# Digital_Inputs.net
KiCad netlist of a schematic drawn in Altium Designer
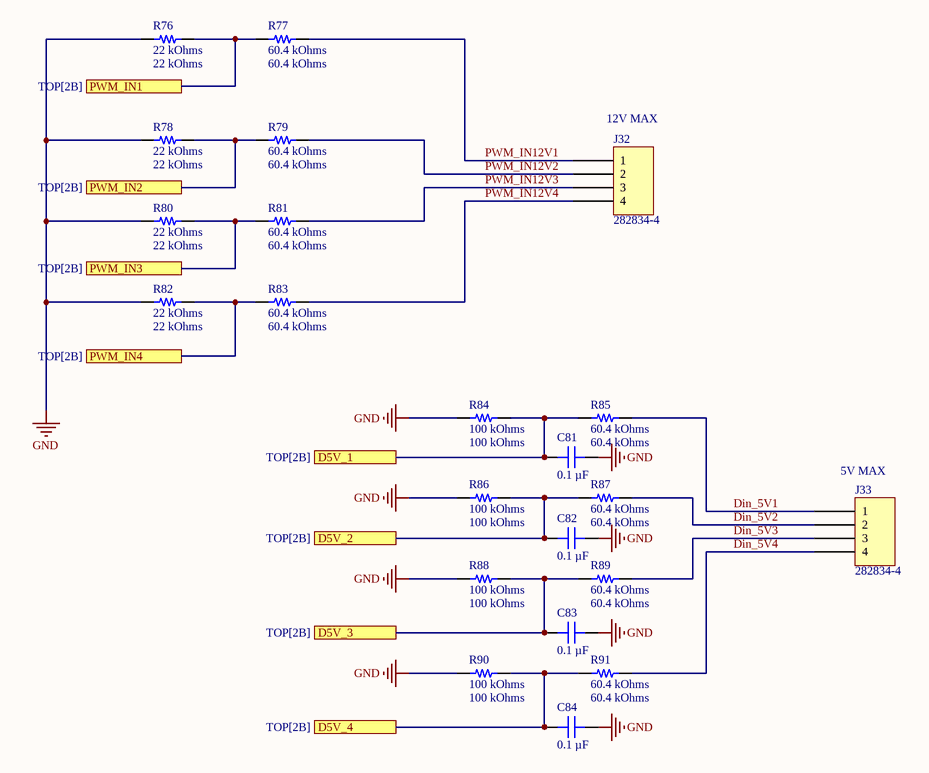
[diagram p0: Digital Inputs.SchDoc]

(export (version "E")
  (design (tool "Eeschema 10.0.6"))
  (components
    (comp (ref "C81")
      (value "0.1 µF")
      (footprint "CAP 0603_1608")
      (description "CAP CER 0.1UF 6.3V X7R 0603")
      (fields
        (field (name "PART NUMBER") "6R3X14W104MV4T")
        (field (name "MANUFACTURER") "Johanson Dielectrics Inc.")
      )
      (libsource (lib "altium_library") (part "Capacitor"))
    )
    (comp (ref "C82")
      (value "0.1 µF")
      (footprint "CAP 0603_1608")
      (description "CAP CER 0.1UF 6.3V X7R 0603")
      (fields
        (field (name "PART NUMBER") "6R3X14W104MV4T")
        (field (name "MANUFACTURER") "Johanson Dielectrics Inc.")
      )
      (libsource (lib "altium_library") (part "Capacitor"))
    )
    (comp (ref "C83")
      (value "0.1 µF")
      (footprint "CAP 0603_1608")
      (description "CAP CER 0.1UF 6.3V X7R 0603")
      (fields
        (field (name "PART NUMBER") "6R3X14W104MV4T")
        (field (name "MANUFACTURER") "Johanson Dielectrics Inc.")
      )
      (libsource (lib "altium_library") (part "Capacitor"))
    )
    (comp (ref "C84")
      (value "0.1 µF")
      (footprint "CAP 0603_1608")
      (description "CAP CER 0.1UF 6.3V X7R 0603")
      (fields
        (field (name "PART NUMBER") "6R3X14W104MV4T")
        (field (name "MANUFACTURER") "Johanson Dielectrics Inc.")
      )
      (libsource (lib "altium_library") (part "Capacitor"))
    )
    (comp (ref "J32")
      (value "282834-4")
      (footprint "TE 282834-4")
      (description "TERM BLK 4P SIDE ENT 2.54MM PCB")
      (fields (field (name "MANUFACTURER") "TE Connectivity AMP Connectors") (field (name "VOLTAGE") "150V"))
      (libsource (lib "altium_library") (part "4 Pin"))
    )
    (comp (ref "J33")
      (value "282834-4")
      (footprint "TE 282834-4")
      (description "TERM BLK 4P SIDE ENT 2.54MM PCB")
      (fields (field (name "MANUFACTURER") "TE Connectivity AMP Connectors") (field (name "VOLTAGE") "150V"))
      (libsource (lib "altium_library") (part "4 Pin"))
    )
    (comp (ref "R76")
      (value "22 kOhms")
      (footprint "RES 0603_1608")
      (description "RES 22K OHM 1% 1/5W 0603")
      (fields (field (name "PART NUMBER") "AC0603FR-7W22KL") (field (name "ALTIUM_VALUE") "22 kOhms"))
      (libsource (lib "altium_library") (part "Resistor"))
    )
    (comp (ref "R77")
      (value "60.4 kOhms")
      (footprint "RES 0603_1608")
      (description "RES SMD 60.4K OHM 1% 1/10W 0603")
      (fields (field (name "PART NUMBER") "AC0603FR-0760K4L") (field (name "ALTIUM_VALUE") "60.4 kOhms"))
      (libsource (lib "altium_library") (part "Resistor"))
    )
    (comp (ref "R78")
      (value "22 kOhms")
      (footprint "RES 0603_1608")
      (description "RES 22K OHM 1% 1/5W 0603")
      (fields (field (name "PART NUMBER") "AC0603FR-7W22KL") (field (name "ALTIUM_VALUE") "22 kOhms"))
      (libsource (lib "altium_library") (part "Resistor"))
    )
    (comp (ref "R79")
      (value "60.4 kOhms")
      (footprint "RES 0603_1608")
      (description "RES SMD 60.4K OHM 1% 1/10W 0603")
      (fields (field (name "PART NUMBER") "AC0603FR-0760K4L") (field (name "ALTIUM_VALUE") "60.4 kOhms"))
      (libsource (lib "altium_library") (part "Resistor"))
    )
    (comp (ref "R80")
      (value "22 kOhms")
      (footprint "RES 0603_1608")
      (description "RES 22K OHM 1% 1/5W 0603")
      (fields (field (name "PART NUMBER") "AC0603FR-7W22KL") (field (name "ALTIUM_VALUE") "22 kOhms"))
      (libsource (lib "altium_library") (part "Resistor"))
    )
    (comp (ref "R81")
      (value "60.4 kOhms")
      (footprint "RES 0603_1608")
      (description "RES SMD 60.4K OHM 1% 1/10W 0603")
      (fields (field (name "PART NUMBER") "AC0603FR-0760K4L") (field (name "ALTIUM_VALUE") "60.4 kOhms"))
      (libsource (lib "altium_library") (part "Resistor"))
    )
    (comp (ref "R82")
      (value "22 kOhms")
      (footprint "RES 0603_1608")
      (description "RES 22K OHM 1% 1/5W 0603")
      (fields (field (name "PART NUMBER") "AC0603FR-7W22KL") (field (name "ALTIUM_VALUE") "22 kOhms"))
      (libsource (lib "altium_library") (part "Resistor"))
    )
    (comp (ref "R83")
      (value "60.4 kOhms")
      (footprint "RES 0603_1608")
      (description "RES SMD 60.4K OHM 1% 1/10W 0603")
      (fields (field (name "PART NUMBER") "AC0603FR-0760K4L") (field (name "ALTIUM_VALUE") "60.4 kOhms"))
      (libsource (lib "altium_library") (part "Resistor"))
    )
    (comp (ref "R84")
      (value "100 kOhms")
      (footprint "RES 0603_1608")
      (description "RES SMD 100K OHM 1% 1/10W 0603")
      (fields (field (name "PART NUMBER") "AA0603FR-07100KL") (field (name "ALTIUM_VALUE") "100 kOhms"))
      (libsource (lib "altium_library") (part "Resistor"))
    )
    (comp (ref "R85")
      (value "60.4 kOhms")
      (footprint "RES 0603_1608")
      (description "RES SMD 60.4K OHM 1% 1/10W 0603")
      (fields (field (name "PART NUMBER") "AC0603FR-0760K4L") (field (name "ALTIUM_VALUE") "60.4 kOhms"))
      (libsource (lib "altium_library") (part "Resistor"))
    )
    (comp (ref "R86")
      (value "100 kOhms")
      (footprint "RES 0603_1608")
      (description "RES SMD 100K OHM 1% 1/10W 0603")
      (fields (field (name "PART NUMBER") "AA0603FR-07100KL") (field (name "ALTIUM_VALUE") "100 kOhms"))
      (libsource (lib "altium_library") (part "Resistor"))
    )
    (comp (ref "R87")
      (value "60.4 kOhms")
      (footprint "RES 0603_1608")
      (description "RES SMD 60.4K OHM 1% 1/10W 0603")
      (fields (field (name "PART NUMBER") "AC0603FR-0760K4L") (field (name "ALTIUM_VALUE") "60.4 kOhms"))
      (libsource (lib "altium_library") (part "Resistor"))
    )
    (comp (ref "R88")
      (value "100 kOhms")
      (footprint "RES 0603_1608")
      (description "RES SMD 100K OHM 1% 1/10W 0603")
      (fields (field (name "PART NUMBER") "AA0603FR-07100KL") (field (name "ALTIUM_VALUE") "100 kOhms"))
      (libsource (lib "altium_library") (part "Resistor"))
    )
    (comp (ref "R89")
      (value "60.4 kOhms")
      (footprint "RES 0603_1608")
      (description "RES SMD 60.4K OHM 1% 1/10W 0603")
      (fields (field (name "PART NUMBER") "AC0603FR-0760K4L") (field (name "ALTIUM_VALUE") "60.4 kOhms"))
      (libsource (lib "altium_library") (part "Resistor"))
    )
    (comp (ref "R90")
      (value "100 kOhms")
      (footprint "RES 0603_1608")
      (description "RES SMD 100K OHM 1% 1/10W 0603")
      (fields (field (name "PART NUMBER") "AA0603FR-07100KL") (field (name "ALTIUM_VALUE") "100 kOhms"))
      (libsource (lib "altium_library") (part "Resistor"))
    )
    (comp (ref "R91")
      (value "60.4 kOhms")
      (footprint "RES 0603_1608")
      (description "RES SMD 60.4K OHM 1% 1/10W 0603")
      (fields (field (name "PART NUMBER") "AC0603FR-0760K4L") (field (name "ALTIUM_VALUE") "60.4 kOhms"))
      (libsource (lib "altium_library") (part "Resistor"))
    )
  )
  (nets
    (net (code "1") (name "/D5V_1") (class "Default")
      (node (ref "C81") (pin "1") (pinfunction "1_1") (pintype "passive"))
      (node (ref "R84") (pin "2") (pinfunction "2_2") (pintype "passive"))
      (node (ref "R85") (pin "1") (pinfunction "1_1") (pintype "passive"))
    )
    (net (code "2") (name "/D5V_2") (class "Default")
      (node (ref "C82") (pin "1") (pinfunction "1_1") (pintype "passive"))
      (node (ref "R86") (pin "2") (pinfunction "2_2") (pintype "passive"))
      (node (ref "R87") (pin "1") (pinfunction "1_1") (pintype "passive"))
    )
    (net (code "3") (name "/D5V_3") (class "Default")
      (node (ref "C83") (pin "1") (pinfunction "1_1") (pintype "passive"))
      (node (ref "R88") (pin "2") (pinfunction "2_2") (pintype "passive"))
      (node (ref "R89") (pin "1") (pinfunction "1_1") (pintype "passive"))
    )
    (net (code "4") (name "/D5V_4") (class "Default")
      (node (ref "C84") (pin "1") (pinfunction "1_1") (pintype "passive"))
      (node (ref "R90") (pin "2") (pinfunction "2_2") (pintype "passive"))
      (node (ref "R91") (pin "1") (pinfunction "1_1") (pintype "passive"))
    )
    (net (code "5") (name "/Din_5V1") (class "Default")
      (node (ref "J33") (pin "1") (pinfunction "1_1") (pintype "passive"))
      (node (ref "R85") (pin "2") (pinfunction "2_2") (pintype "passive"))
    )
    (net (code "6") (name "/Din_5V2") (class "Default")
      (node (ref "J33") (pin "2") (pinfunction "2_2") (pintype "passive"))
      (node (ref "R87") (pin "2") (pinfunction "2_2") (pintype "passive"))
    )
    (net (code "7") (name "/Din_5V3") (class "Default")
      (node (ref "J33") (pin "3") (pinfunction "3_3") (pintype "passive"))
      (node (ref "R89") (pin "2") (pinfunction "2_2") (pintype "passive"))
    )
    (net (code "8") (name "/Din_5V4") (class "Default")
      (node (ref "J33") (pin "4") (pinfunction "4_4") (pintype "passive"))
      (node (ref "R91") (pin "2") (pinfunction "2_2") (pintype "passive"))
    )
    (net (code "9") (name "/PWM_IN1") (class "Default")
      (node (ref "R76") (pin "1") (pinfunction "1_1") (pintype "passive"))
      (node (ref "R77") (pin "2") (pinfunction "2_2") (pintype "passive"))
    )
    (net (code "10") (name "/PWM_IN2") (class "Default")
      (node (ref "R78") (pin "1") (pinfunction "1_1") (pintype "passive"))
      (node (ref "R79") (pin "2") (pinfunction "2_2") (pintype "passive"))
    )
    (net (code "11") (name "/PWM_IN3") (class "Default")
      (node (ref "R80") (pin "1") (pinfunction "1_1") (pintype "passive"))
      (node (ref "R81") (pin "2") (pinfunction "2_2") (pintype "passive"))
    )
    (net (code "12") (name "/PWM_IN4") (class "Default")
      (node (ref "R82") (pin "1") (pinfunction "1_1") (pintype "passive"))
      (node (ref "R83") (pin "2") (pinfunction "2_2") (pintype "passive"))
    )
    (net (code "13") (name "/PWM_IN12V1") (class "Default")
      (node (ref "J32") (pin "1") (pinfunction "1_1") (pintype "passive"))
      (node (ref "R77") (pin "1") (pinfunction "1_1") (pintype "passive"))
    )
    (net (code "14") (name "/PWM_IN12V2") (class "Default")
      (node (ref "J32") (pin "2") (pinfunction "2_2") (pintype "passive"))
      (node (ref "R79") (pin "1") (pinfunction "1_1") (pintype "passive"))
    )
    (net (code "15") (name "/PWM_IN12V3") (class "Default")
      (node (ref "J32") (pin "3") (pinfunction "3_3") (pintype "passive"))
      (node (ref "R81") (pin "1") (pinfunction "1_1") (pintype "passive"))
    )
    (net (code "16") (name "/PWM_IN12V4") (class "Default")
      (node (ref "J32") (pin "4") (pinfunction "4_4") (pintype "passive"))
      (node (ref "R83") (pin "1") (pinfunction "1_1") (pintype "passive"))
    )
    (net (code "17") (name "GND") (class "Default")
      (node (ref "C81") (pin "2") (pinfunction "2_2") (pintype "passive"))
      (node (ref "C82") (pin "2") (pinfunction "2_2") (pintype "passive"))
      (node (ref "C83") (pin "2") (pinfunction "2_2") (pintype "passive"))
      (node (ref "C84") (pin "2") (pinfunction "2_2") (pintype "passive"))
      (node (ref "R76") (pin "2") (pinfunction "2_2") (pintype "passive"))
      (node (ref "R78") (pin "2") (pinfunction "2_2") (pintype "passive"))
      (node (ref "R80") (pin "2") (pinfunction "2_2") (pintype "passive"))
      (node (ref "R82") (pin "2") (pinfunction "2_2") (pintype "passive"))
      (node (ref "R84") (pin "1") (pinfunction "1_1") (pintype "passive"))
      (node (ref "R86") (pin "1") (pinfunction "1_1") (pintype "passive"))
      (node (ref "R88") (pin "1") (pinfunction "1_1") (pintype "passive"))
      (node (ref "R90") (pin "1") (pinfunction "1_1") (pintype "passive"))
    )
  )
)
